# tick-display-mk-2.net
KiCad netlist of a schematic drawn in EAGLE
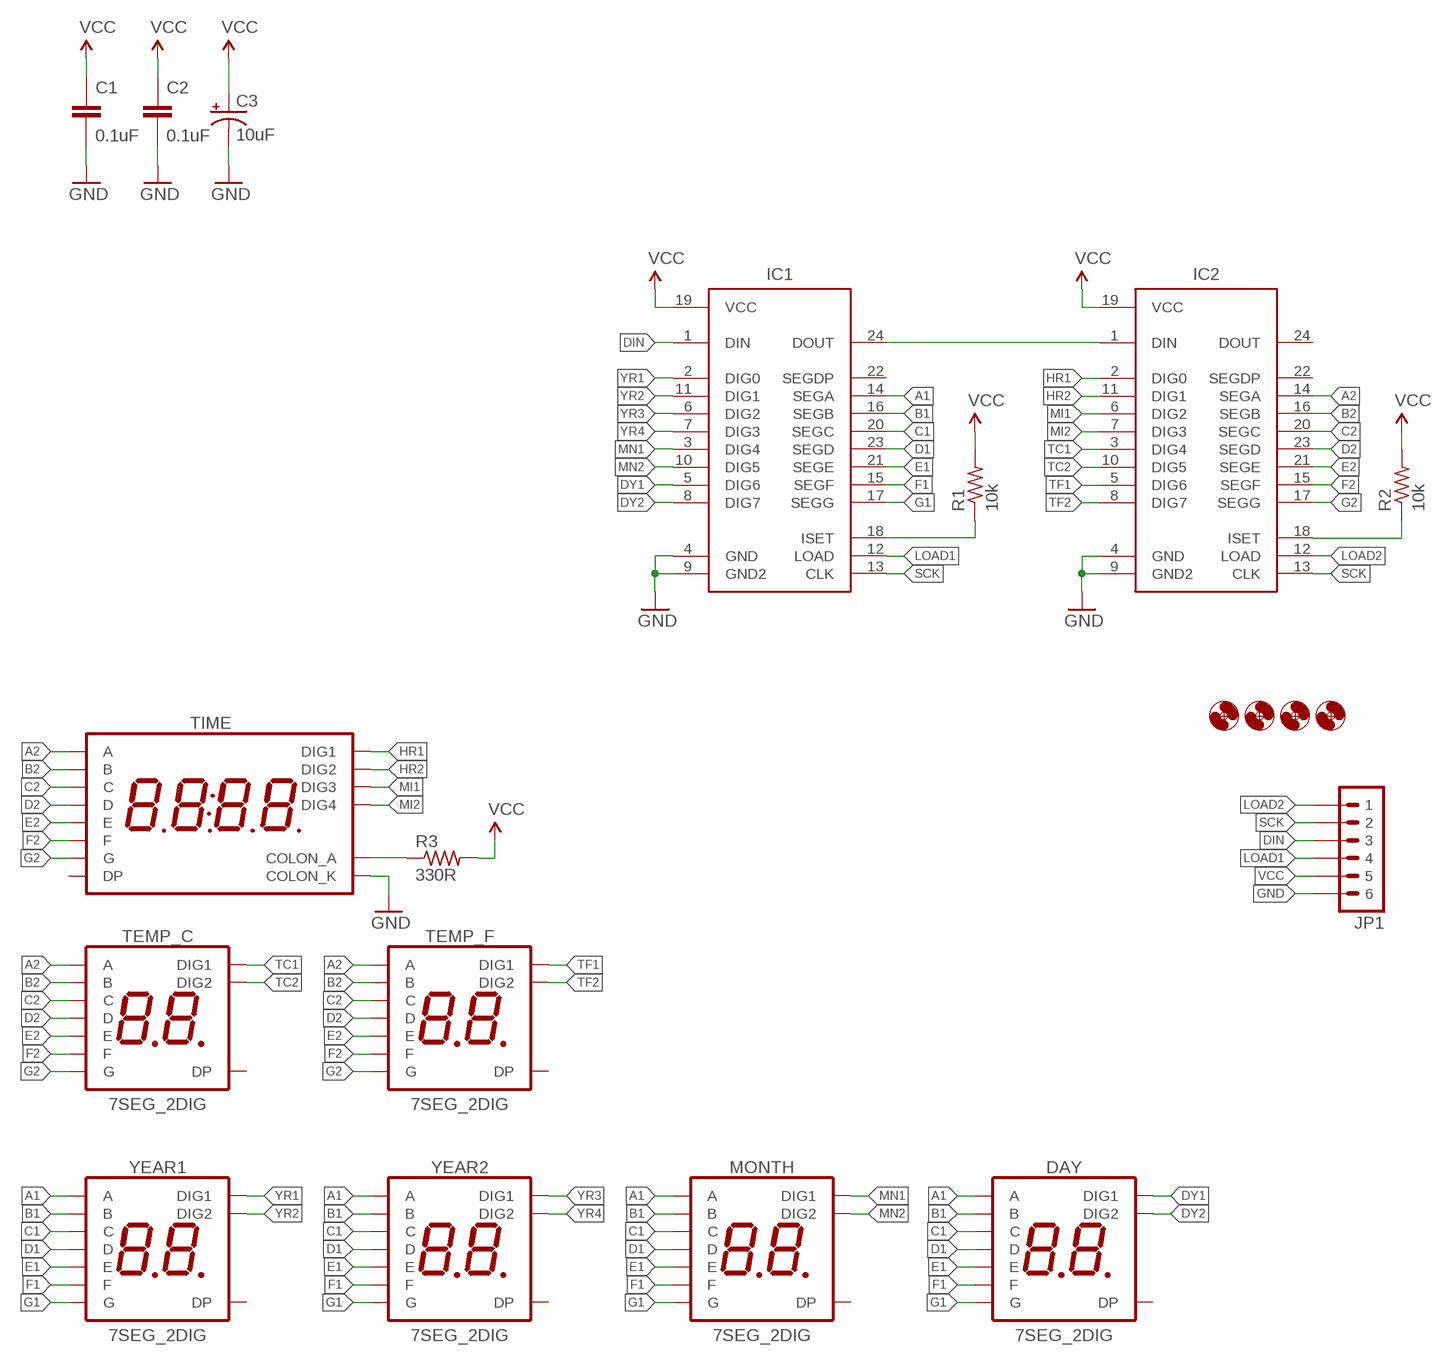
[diagram p0: schematic, sheet 1]

(export (version "E")
  (design (tool "Eeschema 10.0.6"))
  (components
    (comp (ref "C1")
      (value "0.1uF")
      (footprint "eagle-import:C025-024X044")
      (libsource (lib "eagle-import") (part "CAPACITOR-CERAMIC025-024X044"))
    )
    (comp (ref "C2")
      (value "0.1uF")
      (footprint "eagle-import:C025-024X044")
      (libsource (lib "eagle-import") (part "CAPACITOR-CERAMIC025-024X044"))
    )
    (comp (ref "C3")
      (value "10uF")
      (footprint "eagle-import:E2-5")
      (libsource (lib "eagle-import") (part "CAPACITOR-POLARIZEDE2-5"))
    )
    (comp (ref "DAY")
      (value "7SEG_2DIG")
      (footprint "eagle-import:7SEG_2DIG_14MM")
      (libsource (lib "eagle-import") (part "7SEG_2DIG"))
    )
    (comp (ref "H1")
      (value "HOLE#2")
      (footprint "eagle-import:HOLE-#2")
      (libsource (lib "eagle-import") (part "HOLE#2"))
    )
    (comp (ref "H2")
      (value "HOLE#2")
      (footprint "eagle-import:HOLE-#2")
      (libsource (lib "eagle-import") (part "HOLE#2"))
    )
    (comp (ref "H3")
      (value "HOLE#2")
      (footprint "eagle-import:HOLE-#2")
      (libsource (lib "eagle-import") (part "HOLE#2"))
    )
    (comp (ref "H4")
      (value "HOLE#2")
      (footprint "eagle-import:HOLE-#2")
      (libsource (lib "eagle-import") (part "HOLE#2"))
    )
    (comp (ref "IC1")
      (value "MAX7219")
      (footprint "eagle-import:DIL24")
      (libsource (lib "eagle-import") (part "MAX7219DIP"))
    )
    (comp (ref "IC2")
      (value "MAX7219")
      (footprint "eagle-import:DIL24")
      (libsource (lib "eagle-import") (part "MAX7219DIP"))
    )
    (comp (ref "JP1")
      (value "M06JST-PH-PTH-VERT")
      (footprint "eagle-import:JST-6-PH-VERT-PTH")
      (libsource (lib "eagle-import") (part "M06JST-PH-PTH-VERT"))
    )
    (comp (ref "MONTH")
      (value "7SEG_2DIG")
      (footprint "eagle-import:7SEG_2DIG_14MM")
      (libsource (lib "eagle-import") (part "7SEG_2DIG"))
    )
    (comp (ref "R1")
      (value "10k")
      (footprint "eagle-import:RESISTOR-AXIAL-PTH-5.08MM")
      (libsource (lib "eagle-import") (part "RESISTORPTH-AXIAL-5.08MM"))
    )
    (comp (ref "R2")
      (value "10k")
      (footprint "eagle-import:RESISTOR-AXIAL-PTH-5.08MM")
      (libsource (lib "eagle-import") (part "RESISTORPTH-AXIAL-5.08MM"))
    )
    (comp (ref "R3")
      (value "330R")
      (footprint "eagle-import:RESISTOR-AXIAL-PTH-5.08MM")
      (libsource (lib "eagle-import") (part "RESISTORPTH-AXIAL-5.08MM"))
    )
    (comp (ref "TEMP_C")
      (value "7SEG_2DIG")
      (footprint "eagle-import:7SEG_2DIG_14MM")
      (libsource (lib "eagle-import") (part "7SEG_2DIG"))
    )
    (comp (ref "TEMP_F")
      (value "7SEG_2DIG")
      (footprint "eagle-import:7SEG_2DIG_14MM")
      (libsource (lib "eagle-import") (part "7SEG_2DIG"))
    )
    (comp (ref "TIME")
      (value "7SED_4DIGIT_14MM14.2MM-CC")
      (footprint "eagle-import:7SEG_4DIG")
      (libsource (lib "eagle-import") (part "7SED_4DIGIT_14MM14.2MM-CC"))
    )
    (comp (ref "YEAR1")
      (value "7SEG_2DIG")
      (footprint "eagle-import:7SEG_2DIG_14MM")
      (libsource (lib "eagle-import") (part "7SEG_2DIG"))
    )
    (comp (ref "YEAR2")
      (value "7SEG_2DIG")
      (footprint "eagle-import:7SEG_2DIG_14MM")
      (libsource (lib "eagle-import") (part "7SEG_2DIG"))
    )
  )
  (nets
    (net (code "1") (name "A1") (class "Default")
      (node (ref "DAY") (pin "4") (pinfunction "A_4") (pintype "passive"))
      (node (ref "IC1") (pin "14") (pinfunction "SEGA_14") (pintype "bidirectional"))
      (node (ref "MONTH") (pin "4") (pinfunction "A_4") (pintype "passive"))
      (node (ref "YEAR1") (pin "4") (pinfunction "A_4") (pintype "passive"))
      (node (ref "YEAR2") (pin "4") (pinfunction "A_4") (pintype "passive"))
    )
    (net (code "2") (name "A2") (class "Default")
      (node (ref "IC2") (pin "14") (pinfunction "SEGA_14") (pintype "bidirectional"))
      (node (ref "TEMP_C") (pin "4") (pinfunction "A_4") (pintype "passive"))
      (node (ref "TEMP_F") (pin "4") (pinfunction "A_4") (pintype "passive"))
      (node (ref "TIME") (pin "P$13") (pinfunction "A_P$13") (pintype "passive"))
    )
    (net (code "3") (name "B1") (class "Default")
      (node (ref "DAY") (pin "3") (pinfunction "B_3") (pintype "passive"))
      (node (ref "IC1") (pin "16") (pinfunction "SEGB_16") (pintype "bidirectional"))
      (node (ref "MONTH") (pin "3") (pinfunction "B_3") (pintype "passive"))
      (node (ref "YEAR1") (pin "3") (pinfunction "B_3") (pintype "passive"))
      (node (ref "YEAR2") (pin "3") (pinfunction "B_3") (pintype "passive"))
    )
    (net (code "4") (name "B2") (class "Default")
      (node (ref "IC2") (pin "16") (pinfunction "SEGB_16") (pintype "bidirectional"))
      (node (ref "TEMP_C") (pin "3") (pinfunction "B_3") (pintype "passive"))
      (node (ref "TEMP_F") (pin "3") (pinfunction "B_3") (pintype "passive"))
      (node (ref "TIME") (pin "P$9") (pinfunction "B_P$9") (pintype "passive"))
    )
    (net (code "5") (name "C1") (class "Default")
      (node (ref "DAY") (pin "9") (pinfunction "C_9") (pintype "passive"))
      (node (ref "IC1") (pin "20") (pinfunction "SEGC_20") (pintype "bidirectional"))
      (node (ref "MONTH") (pin "9") (pinfunction "C_9") (pintype "passive"))
      (node (ref "YEAR1") (pin "9") (pinfunction "C_9") (pintype "passive"))
      (node (ref "YEAR2") (pin "9") (pinfunction "C_9") (pintype "passive"))
    )
    (net (code "6") (name "C2") (class "Default")
      (node (ref "IC2") (pin "20") (pinfunction "SEGC_20") (pintype "bidirectional"))
      (node (ref "TEMP_C") (pin "9") (pinfunction "C_9") (pintype "passive"))
      (node (ref "TEMP_F") (pin "9") (pinfunction "C_9") (pintype "passive"))
      (node (ref "TIME") (pin "P$4") (pinfunction "C_P$4") (pintype "passive"))
    )
    (net (code "7") (name "D1") (class "Default")
      (node (ref "DAY") (pin "8") (pinfunction "D_8") (pintype "passive"))
      (node (ref "IC1") (pin "23") (pinfunction "SEGD_23") (pintype "bidirectional"))
      (node (ref "MONTH") (pin "8") (pinfunction "D_8") (pintype "passive"))
      (node (ref "YEAR1") (pin "8") (pinfunction "D_8") (pintype "passive"))
      (node (ref "YEAR2") (pin "8") (pinfunction "D_8") (pintype "passive"))
    )
    (net (code "8") (name "D2") (class "Default")
      (node (ref "IC2") (pin "23") (pinfunction "SEGD_23") (pintype "bidirectional"))
      (node (ref "TEMP_C") (pin "8") (pinfunction "D_8") (pintype "passive"))
      (node (ref "TEMP_F") (pin "8") (pinfunction "D_8") (pintype "passive"))
      (node (ref "TIME") (pin "P$2") (pinfunction "D_P$2") (pintype "passive"))
    )
    (net (code "9") (name "DIN") (class "Default")
      (node (ref "IC1") (pin "1") (pinfunction "DIN_1") (pintype "bidirectional"))
      (node (ref "JP1") (pin "3") (pinfunction "3_3") (pintype "passive"))
    )
    (net (code "10") (name "DY1") (class "Default")
      (node (ref "DAY") (pin "5") (pinfunction "DIG1_5") (pintype "passive"))
      (node (ref "IC1") (pin "5") (pinfunction "DIG6_5") (pintype "bidirectional"))
    )
    (net (code "11") (name "DY2") (class "Default")
      (node (ref "DAY") (pin "10") (pinfunction "DIG2_10") (pintype "passive"))
      (node (ref "IC1") (pin "8") (pinfunction "DIG7_8") (pintype "bidirectional"))
    )
    (net (code "12") (name "E1") (class "Default")
      (node (ref "DAY") (pin "6") (pinfunction "E_6") (pintype "passive"))
      (node (ref "IC1") (pin "21") (pinfunction "SEGE_21") (pintype "bidirectional"))
      (node (ref "MONTH") (pin "6") (pinfunction "E_6") (pintype "passive"))
      (node (ref "YEAR1") (pin "6") (pinfunction "E_6") (pintype "passive"))
      (node (ref "YEAR2") (pin "6") (pinfunction "E_6") (pintype "passive"))
    )
    (net (code "13") (name "E2") (class "Default")
      (node (ref "IC2") (pin "21") (pinfunction "SEGE_21") (pintype "bidirectional"))
      (node (ref "TEMP_C") (pin "6") (pinfunction "E_6") (pintype "passive"))
      (node (ref "TEMP_F") (pin "6") (pinfunction "E_6") (pintype "passive"))
      (node (ref "TIME") (pin "P$1") (pinfunction "E_P$1") (pintype "passive"))
    )
    (net (code "14") (name "F1") (class "Default")
      (node (ref "DAY") (pin "7") (pinfunction "F_7") (pintype "passive"))
      (node (ref "IC1") (pin "15") (pinfunction "SEGF_15") (pintype "bidirectional"))
      (node (ref "MONTH") (pin "7") (pinfunction "F_7") (pintype "passive"))
      (node (ref "YEAR1") (pin "7") (pinfunction "F_7") (pintype "passive"))
      (node (ref "YEAR2") (pin "7") (pinfunction "F_7") (pintype "passive"))
    )
    (net (code "15") (name "F2") (class "Default")
      (node (ref "IC2") (pin "15") (pinfunction "SEGF_15") (pintype "bidirectional"))
      (node (ref "TEMP_C") (pin "7") (pinfunction "F_7") (pintype "passive"))
      (node (ref "TEMP_F") (pin "7") (pinfunction "F_7") (pintype "passive"))
      (node (ref "TIME") (pin "P$12") (pinfunction "F_P$12") (pintype "passive"))
    )
    (net (code "16") (name "G1") (class "Default")
      (node (ref "DAY") (pin "1") (pinfunction "G_1") (pintype "passive"))
      (node (ref "IC1") (pin "17") (pinfunction "SEGG_17") (pintype "bidirectional"))
      (node (ref "MONTH") (pin "1") (pinfunction "G_1") (pintype "passive"))
      (node (ref "YEAR1") (pin "1") (pinfunction "G_1") (pintype "passive"))
      (node (ref "YEAR2") (pin "1") (pinfunction "G_1") (pintype "passive"))
    )
    (net (code "17") (name "G2") (class "Default")
      (node (ref "IC2") (pin "17") (pinfunction "SEGG_17") (pintype "bidirectional"))
      (node (ref "TEMP_C") (pin "1") (pinfunction "G_1") (pintype "passive"))
      (node (ref "TEMP_F") (pin "1") (pinfunction "G_1") (pintype "passive"))
      (node (ref "TIME") (pin "P$5") (pinfunction "G_P$5") (pintype "passive"))
    )
    (net (code "18") (name "GND") (class "Default")
      (node (ref "C1") (pin "2") (pinfunction "2_2") (pintype "passive"))
      (node (ref "C2") (pin "2") (pinfunction "2_2") (pintype "passive"))
      (node (ref "C3") (pin "-") (pinfunction "-_-") (pintype "passive"))
      (node (ref "IC1") (pin "4") (pinfunction "GND_4") (pintype "bidirectional"))
      (node (ref "IC1") (pin "9") (pinfunction "GND2_9") (pintype "bidirectional"))
      (node (ref "IC2") (pin "4") (pinfunction "GND_4") (pintype "bidirectional"))
      (node (ref "IC2") (pin "9") (pinfunction "GND2_9") (pintype "bidirectional"))
      (node (ref "JP1") (pin "6") (pinfunction "6_6") (pintype "passive"))
      (node (ref "TIME") (pin "P$7") (pinfunction "COLON_K_P$7") (pintype "passive"))
    )
    (net (code "19") (name "HR1") (class "Default")
      (node (ref "IC2") (pin "2") (pinfunction "DIG0_2") (pintype "bidirectional"))
      (node (ref "TIME") (pin "P$14") (pinfunction "DIG1_P$14") (pintype "passive"))
    )
    (net (code "20") (name "HR2") (class "Default")
      (node (ref "IC2") (pin "11") (pinfunction "DIG1_11") (pintype "bidirectional"))
      (node (ref "TIME") (pin "P$11") (pinfunction "DIG2_P$11") (pintype "passive"))
    )
    (net (code "21") (name "LOAD1") (class "Default")
      (node (ref "IC1") (pin "12") (pinfunction "LOAD_12") (pintype "bidirectional"))
      (node (ref "JP1") (pin "4") (pinfunction "4_4") (pintype "passive"))
    )
    (net (code "22") (name "LOAD2") (class "Default")
      (node (ref "IC2") (pin "12") (pinfunction "LOAD_12") (pintype "bidirectional"))
      (node (ref "JP1") (pin "1") (pinfunction "1_1") (pintype "passive"))
    )
    (net (code "23") (name "MI1") (class "Default")
      (node (ref "IC2") (pin "6") (pinfunction "DIG2_6") (pintype "bidirectional"))
      (node (ref "TIME") (pin "P$10") (pinfunction "DIG3_P$10") (pintype "passive"))
    )
    (net (code "24") (name "MI2") (class "Default")
      (node (ref "IC2") (pin "7") (pinfunction "DIG3_7") (pintype "bidirectional"))
      (node (ref "TIME") (pin "P$6") (pinfunction "DIG4_P$6") (pintype "passive"))
    )
    (net (code "25") (name "MN1") (class "Default")
      (node (ref "IC1") (pin "3") (pinfunction "DIG4_3") (pintype "bidirectional"))
      (node (ref "MONTH") (pin "5") (pinfunction "DIG1_5") (pintype "passive"))
    )
    (net (code "26") (name "MN2") (class "Default")
      (node (ref "IC1") (pin "10") (pinfunction "DIG5_10") (pintype "bidirectional"))
      (node (ref "MONTH") (pin "10") (pinfunction "DIG2_10") (pintype "passive"))
    )
    (net (code "27") (name "Net-(IC1-DOUT)") (class "Default")
      (node (ref "IC1") (pin "24") (pinfunction "DOUT_24") (pintype "bidirectional"))
      (node (ref "IC2") (pin "1") (pinfunction "DIN_1") (pintype "bidirectional"))
    )
    (net (code "28") (name "Net-(IC1-ISET)") (class "Default")
      (node (ref "IC1") (pin "18") (pinfunction "ISET_18") (pintype "bidirectional"))
      (node (ref "R1") (pin "P$1") (pinfunction "1_P$1") (pintype "passive"))
    )
    (net (code "29") (name "Net-(IC2-ISET)") (class "Default")
      (node (ref "IC2") (pin "18") (pinfunction "ISET_18") (pintype "bidirectional"))
      (node (ref "R2") (pin "P$1") (pinfunction "1_P$1") (pintype "passive"))
    )
    (net (code "30") (name "Net-(R3-1)") (class "Default")
      (node (ref "R3") (pin "P$1") (pinfunction "1_P$1") (pintype "passive"))
      (node (ref "TIME") (pin "P$8") (pinfunction "COLON_A_P$8") (pintype "passive"))
    )
    (net (code "31") (name "SCK") (class "Default")
      (node (ref "IC1") (pin "13") (pinfunction "CLK_13") (pintype "bidirectional"))
      (node (ref "IC2") (pin "13") (pinfunction "CLK_13") (pintype "bidirectional"))
      (node (ref "JP1") (pin "2") (pinfunction "2_2") (pintype "passive"))
    )
    (net (code "32") (name "TC1") (class "Default")
      (node (ref "IC2") (pin "3") (pinfunction "DIG4_3") (pintype "bidirectional"))
      (node (ref "TEMP_C") (pin "5") (pinfunction "DIG1_5") (pintype "passive"))
    )
    (net (code "33") (name "TC2") (class "Default")
      (node (ref "IC2") (pin "10") (pinfunction "DIG5_10") (pintype "bidirectional"))
      (node (ref "TEMP_C") (pin "10") (pinfunction "DIG2_10") (pintype "passive"))
    )
    (net (code "34") (name "TF1") (class "Default")
      (node (ref "IC2") (pin "5") (pinfunction "DIG6_5") (pintype "bidirectional"))
      (node (ref "TEMP_F") (pin "5") (pinfunction "DIG1_5") (pintype "passive"))
    )
    (net (code "35") (name "TF2") (class "Default")
      (node (ref "IC2") (pin "8") (pinfunction "DIG7_8") (pintype "bidirectional"))
      (node (ref "TEMP_F") (pin "10") (pinfunction "DIG2_10") (pintype "passive"))
    )
    (net (code "36") (name "VCC") (class "Default")
      (node (ref "C1") (pin "1") (pinfunction "1_1") (pintype "passive"))
      (node (ref "C2") (pin "1") (pinfunction "1_1") (pintype "passive"))
      (node (ref "C3") (pin "+") (pinfunction "+_+") (pintype "passive"))
      (node (ref "IC1") (pin "19") (pinfunction "VCC_19") (pintype "bidirectional"))
      (node (ref "IC2") (pin "19") (pinfunction "VCC_19") (pintype "bidirectional"))
      (node (ref "JP1") (pin "5") (pinfunction "5_5") (pintype "passive"))
      (node (ref "R1") (pin "P$2") (pinfunction "2_P$2") (pintype "passive"))
      (node (ref "R2") (pin "P$2") (pinfunction "2_P$2") (pintype "passive"))
      (node (ref "R3") (pin "P$2") (pinfunction "2_P$2") (pintype "passive"))
    )
    (net (code "37") (name "YR1") (class "Default")
      (node (ref "IC1") (pin "2") (pinfunction "DIG0_2") (pintype "bidirectional"))
      (node (ref "YEAR1") (pin "5") (pinfunction "DIG1_5") (pintype "passive"))
    )
    (net (code "38") (name "YR2") (class "Default")
      (node (ref "IC1") (pin "11") (pinfunction "DIG1_11") (pintype "bidirectional"))
      (node (ref "YEAR1") (pin "10") (pinfunction "DIG2_10") (pintype "passive"))
    )
    (net (code "39") (name "YR3") (class "Default")
      (node (ref "IC1") (pin "6") (pinfunction "DIG2_6") (pintype "bidirectional"))
      (node (ref "YEAR2") (pin "5") (pinfunction "DIG1_5") (pintype "passive"))
    )
    (net (code "40") (name "YR4") (class "Default")
      (node (ref "IC1") (pin "7") (pinfunction "DIG3_7") (pintype "bidirectional"))
      (node (ref "YEAR2") (pin "10") (pinfunction "DIG2_10") (pintype "passive"))
    )
    (net (code "41") (name "unconnected-(DAY-DP-Pad2)") (class "Default")
      (node (ref "DAY") (pin "2") (pinfunction "DP_2") (pintype "passive"))
    )
    (net (code "42") (name "unconnected-(IC1-SEGDP-Pad22)") (class "Default")
      (node (ref "IC1") (pin "22") (pinfunction "SEGDP_22") (pintype "bidirectional"))
    )
    (net (code "43") (name "unconnected-(IC2-DOUT-Pad24)") (class "Default")
      (node (ref "IC2") (pin "24") (pinfunction "DOUT_24") (pintype "bidirectional"))
    )
    (net (code "44") (name "unconnected-(IC2-SEGDP-Pad22)") (class "Default")
      (node (ref "IC2") (pin "22") (pinfunction "SEGDP_22") (pintype "bidirectional"))
    )
    (net (code "45") (name "unconnected-(MONTH-DP-Pad2)") (class "Default")
      (node (ref "MONTH") (pin "2") (pinfunction "DP_2") (pintype "passive"))
    )
    (net (code "46") (name "unconnected-(TEMP_C-DP-Pad2)") (class "Default")
      (node (ref "TEMP_C") (pin "2") (pinfunction "DP_2") (pintype "passive"))
    )
    (net (code "47") (name "unconnected-(TEMP_F-DP-Pad2)") (class "Default")
      (node (ref "TEMP_F") (pin "2") (pinfunction "DP_2") (pintype "passive"))
    )
    (net (code "48") (name "unconnected-(TIME-DP-PadP$3)") (class "Default")
      (node (ref "TIME") (pin "P$3") (pinfunction "DP_P$3") (pintype "passive"))
    )
    (net (code "49") (name "unconnected-(YEAR1-DP-Pad2)") (class "Default")
      (node (ref "YEAR1") (pin "2") (pinfunction "DP_2") (pintype "passive"))
    )
    (net (code "50") (name "unconnected-(YEAR2-DP-Pad2)") (class "Default")
      (node (ref "YEAR2") (pin "2") (pinfunction "DP_2") (pintype "passive"))
    )
  )
)
